# 1P3W_v1p1.net
KiCad netlist of a schematic drawn in EAGLE
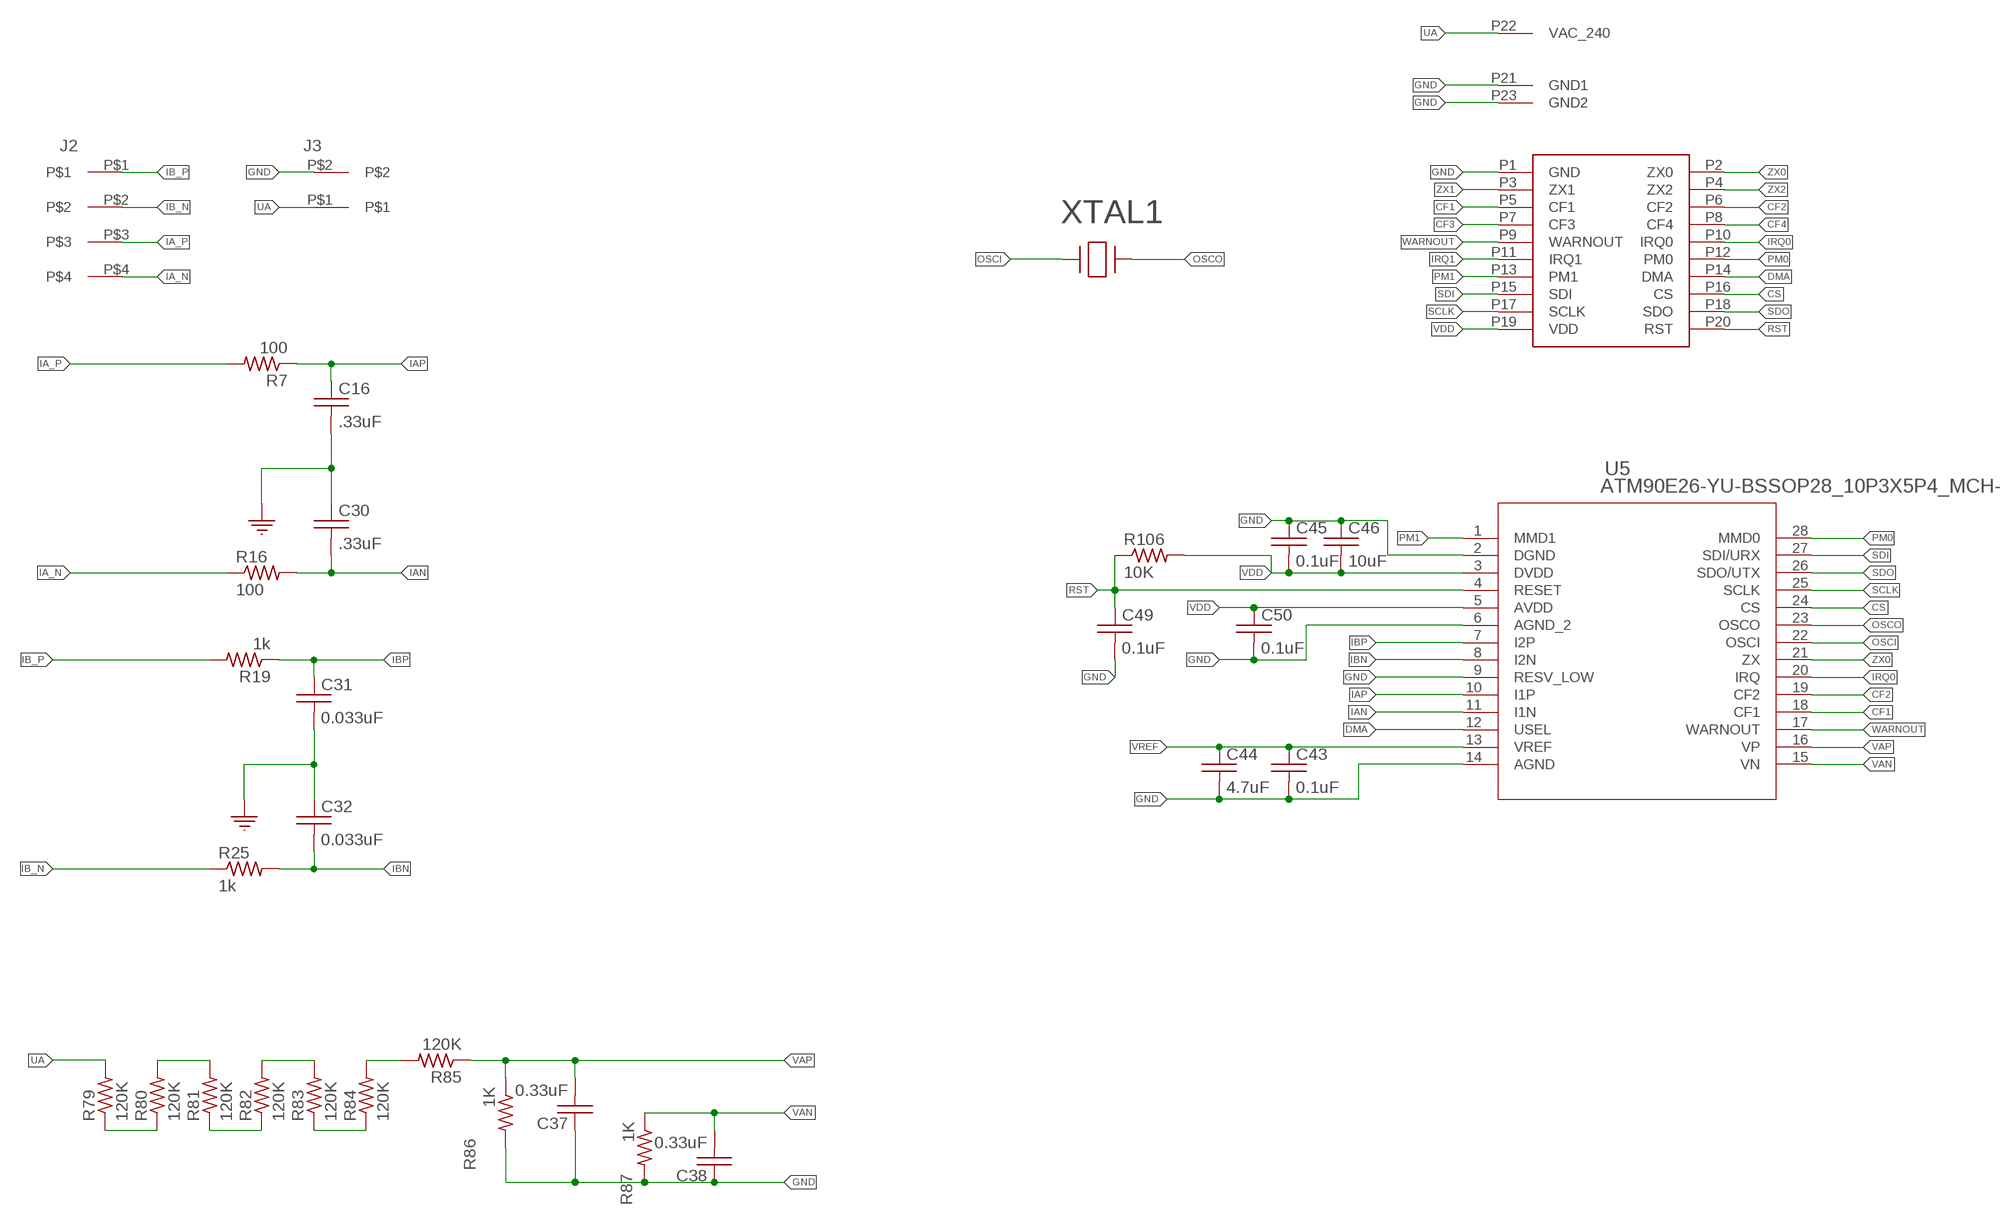
[diagram p0: schematic, sheet 1]

(export (version "E")
  (design (tool "Eeschema 10.0.6"))
  (components
    (comp (ref "C16")
      (value ".33uF")
      (footprint "eagle-import:0402")
      (libsource (lib "eagle-import") (part "C_0402"))
    )
    (comp (ref "C30")
      (value ".33uF")
      (footprint "eagle-import:0402")
      (libsource (lib "eagle-import") (part "C_0402"))
    )
    (comp (ref "C31")
      (value "0.033uF")
      (footprint "eagle-import:0402")
      (libsource (lib "eagle-import") (part "C_0402"))
    )
    (comp (ref "C32")
      (value "0.033uF")
      (footprint "eagle-import:0402")
      (libsource (lib "eagle-import") (part "C_0402"))
    )
    (comp (ref "C37")
      (value "0.33uF")
      (footprint "eagle-import:0402")
      (libsource (lib "eagle-import") (part "C_0402"))
    )
    (comp (ref "C38")
      (value "0.33uF")
      (footprint "eagle-import:0402")
      (libsource (lib "eagle-import") (part "C_0402"))
    )
    (comp (ref "C43")
      (value "0.1uF")
      (footprint "eagle-import:0402")
      (libsource (lib "eagle-import") (part "C_0402"))
    )
    (comp (ref "C44")
      (value "4.7uF")
      (footprint "eagle-import:0402")
      (libsource (lib "eagle-import") (part "C_0402"))
    )
    (comp (ref "C45")
      (value "0.1uF")
      (footprint "eagle-import:0402")
      (libsource (lib "eagle-import") (part "C_0402"))
    )
    (comp (ref "C46")
      (value "10uF")
      (footprint "eagle-import:0402")
      (libsource (lib "eagle-import") (part "C_0402"))
    )
    (comp (ref "C49")
      (value "0.1uF")
      (footprint "eagle-import:0402")
      (libsource (lib "eagle-import") (part "C_0402"))
    )
    (comp (ref "C50")
      (value "0.1uF")
      (footprint "eagle-import:0402")
      (libsource (lib "eagle-import") (part "C_0402"))
    )
    (comp (ref "J2")
      (value "3.81MM_1_X_4_RT_ANGLE_PLUG_HEADER")
      (footprint "eagle-import:1X4_3.81MM_PITCH")
      (libsource (lib "eagle-import") (part "3.81MM_1_X_4_RT_ANGLE_PLUG_HEADER"))
    )
    (comp (ref "J3")
      (value "3.81MM_1_X_2_RT_ANGLE_PLUG_HEADER")
      (footprint "eagle-import:2_3.81MM_PITCH")
      (libsource (lib "eagle-import") (part "3.81MM_1_X_2_RT_ANGLE_PLUG_HEADER"))
    )
    (comp (ref "R7")
      (value "100")
      (footprint "eagle-import:0402")
      (libsource (lib "eagle-import") (part "R_0402"))
    )
    (comp (ref "R16")
      (value "100")
      (footprint "eagle-import:0402")
      (libsource (lib "eagle-import") (part "R_0402"))
    )
    (comp (ref "R19")
      (value "1k")
      (footprint "eagle-import:0402")
      (libsource (lib "eagle-import") (part "R_0402"))
    )
    (comp (ref "R25")
      (value "1k")
      (footprint "eagle-import:0402")
      (libsource (lib "eagle-import") (part "R_0402"))
    )
    (comp (ref "R79")
      (value "120K")
      (footprint "eagle-import:0402")
      (libsource (lib "eagle-import") (part "R_0402"))
    )
    (comp (ref "R80")
      (value "120K")
      (footprint "eagle-import:0402")
      (libsource (lib "eagle-import") (part "R_0402"))
    )
    (comp (ref "R81")
      (value "120K")
      (footprint "eagle-import:0402")
      (libsource (lib "eagle-import") (part "R_0402"))
    )
    (comp (ref "R82")
      (value "120K")
      (footprint "eagle-import:0402")
      (libsource (lib "eagle-import") (part "R_0402"))
    )
    (comp (ref "R83")
      (value "120K")
      (footprint "eagle-import:0402")
      (libsource (lib "eagle-import") (part "R_0402"))
    )
    (comp (ref "R84")
      (value "120K")
      (footprint "eagle-import:0402")
      (libsource (lib "eagle-import") (part "R_0402"))
    )
    (comp (ref "R85")
      (value "120K")
      (footprint "eagle-import:0402")
      (libsource (lib "eagle-import") (part "R_0402"))
    )
    (comp (ref "R86")
      (value "1K")
      (footprint "eagle-import:0402")
      (libsource (lib "eagle-import") (part "R_0402"))
    )
    (comp (ref "R87")
      (value "1K")
      (footprint "eagle-import:0402")
      (libsource (lib "eagle-import") (part "R_0402"))
    )
    (comp (ref "R106")
      (value "10K")
      (footprint "eagle-import:0402")
      (libsource (lib "eagle-import") (part "R_0402"))
    )
    (comp (ref "U$1")
      (value "METER_BASE")
      (footprint "eagle-import:METER_BASE")
      (libsource (lib "eagle-import") (part "METER_BASE"))
    )
    (comp (ref "U5")
      (value "ATM90E26-YU-BSSOP28_10P3X5P4_MCH-M")
      (footprint "eagle-import:SSOP28_10P3X5P4_MCH-M")
      (fields
        (field (name "MANUFACTURER_PART_NUMBER") "ATM90E26-YU-B")
        (field (name "COPYRIGHT") "Copyright (C) 2018 Accelerated Designs. All rights reserved")
      )
      (libsource (lib "eagle-import") (part "ATM90E26-YU-BSSOP28_10P3X5P4_MCH-M"))
    )
    (comp (ref "XTAL1")
      (value "ABLS-8.192MHZ-B2-TXTAL_HC/49US_ABLS_ABR-M")
      (footprint "eagle-import:XTAL_HC_49US_ABLS_ABR-M")
      (fields
        (field (name "MANUFACTURER_PART_NUMBER") "ABLS-8.192MHZ-B2-T")
        (field (name "COPYRIGHT") "Copyright (C) 2018 Accelerated Designs. All rights reserved")
      )
      (libsource (lib "eagle-import") (part "ABLS-8.192MHZ-B2-TXTAL_HC/49US_ABLS_ABR-M"))
    )
  )
  (nets
    (net (code "1") (name "CF1") (class "Default")
      (node (ref "U$1") (pin "P5") (pinfunction "CF1_P5") (pintype "bidirectional"))
      (node (ref "U5") (pin "18") (pinfunction "CF1_18") (pintype "bidirectional"))
    )
    (net (code "2") (name "CF2") (class "Default")
      (node (ref "U$1") (pin "P6") (pinfunction "CF2_P6") (pintype "bidirectional"))
      (node (ref "U5") (pin "19") (pinfunction "CF2_19") (pintype "bidirectional"))
    )
    (net (code "3") (name "CF3") (class "Default")
      (node (ref "U$1") (pin "P7") (pinfunction "CF3_P7") (pintype "bidirectional"))
    )
    (net (code "4") (name "CF4") (class "Default")
      (node (ref "U$1") (pin "P8") (pinfunction "CF4_P8") (pintype "bidirectional"))
    )
    (net (code "5") (name "CS") (class "Default")
      (node (ref "U$1") (pin "P16") (pinfunction "CS_P16") (pintype "bidirectional"))
      (node (ref "U5") (pin "24") (pinfunction "CS_24") (pintype "passive"))
    )
    (net (code "6") (name "DMA") (class "Default")
      (node (ref "U$1") (pin "P14") (pinfunction "DMA_P14") (pintype "bidirectional"))
      (node (ref "U5") (pin "12") (pinfunction "USEL_12") (pintype "passive"))
    )
    (net (code "7") (name "GND") (class "Default")
      (node (ref "C16") (pin "P$2") (pinfunction "2_P$2") (pintype "passive"))
      (node (ref "C30") (pin "P$1") (pinfunction "1_P$1") (pintype "passive"))
      (node (ref "C31") (pin "P$2") (pinfunction "2_P$2") (pintype "passive"))
      (node (ref "C32") (pin "P$1") (pinfunction "1_P$1") (pintype "passive"))
      (node (ref "C37") (pin "P$1") (pinfunction "1_P$1") (pintype "passive"))
      (node (ref "C38") (pin "P$1") (pinfunction "1_P$1") (pintype "passive"))
      (node (ref "C43") (pin "P$2") (pinfunction "2_P$2") (pintype "passive"))
      (node (ref "C44") (pin "P$2") (pinfunction "2_P$2") (pintype "passive"))
      (node (ref "C45") (pin "P$1") (pinfunction "1_P$1") (pintype "passive"))
      (node (ref "C46") (pin "P$1") (pinfunction "1_P$1") (pintype "passive"))
      (node (ref "C49") (pin "P$2") (pinfunction "2_P$2") (pintype "passive"))
      (node (ref "C50") (pin "P$2") (pinfunction "2_P$2") (pintype "passive"))
      (node (ref "J3") (pin "P$2") (pinfunction "P$2_P$2") (pintype "bidirectional"))
      (node (ref "R86") (pin "P$2") (pinfunction "2_P$2") (pintype "passive"))
      (node (ref "R87") (pin "P$2") (pinfunction "2_P$2") (pintype "passive"))
      (node (ref "U$1") (pin "P1") (pinfunction "GND_P1") (pintype "bidirectional"))
      (node (ref "U$1") (pin "P21") (pinfunction "GND1_P21") (pintype "bidirectional"))
      (node (ref "U$1") (pin "P23") (pinfunction "GND2_P23") (pintype "bidirectional"))
      (node (ref "U5") (pin "14") (pinfunction "AGND_14") (pintype "passive"))
      (node (ref "U5") (pin "2") (pinfunction "DGND_2") (pintype "passive"))
      (node (ref "U5") (pin "6") (pinfunction "AGND_2_6") (pintype "passive"))
      (node (ref "U5") (pin "9") (pinfunction "RESV_LOW_9") (pintype "passive"))
    )
    (net (code "8") (name "IAN") (class "Default")
      (node (ref "C30") (pin "P$2") (pinfunction "2_P$2") (pintype "passive"))
      (node (ref "R16") (pin "P$2") (pinfunction "2_P$2") (pintype "passive"))
      (node (ref "U5") (pin "11") (pinfunction "I1N_11") (pintype "bidirectional"))
    )
    (net (code "9") (name "IAP") (class "Default")
      (node (ref "C16") (pin "P$1") (pinfunction "1_P$1") (pintype "passive"))
      (node (ref "R7") (pin "P$1") (pinfunction "1_P$1") (pintype "passive"))
      (node (ref "U5") (pin "10") (pinfunction "I1P_10") (pintype "bidirectional"))
    )
    (net (code "10") (name "IA_N") (class "Default")
      (node (ref "J2") (pin "P$4") (pinfunction "P$4_P$4") (pintype "bidirectional"))
      (node (ref "R16") (pin "P$1") (pinfunction "1_P$1") (pintype "passive"))
    )
    (net (code "11") (name "IA_P") (class "Default")
      (node (ref "J2") (pin "P$3") (pinfunction "P$3_P$3") (pintype "bidirectional"))
      (node (ref "R7") (pin "P$2") (pinfunction "2_P$2") (pintype "passive"))
    )
    (net (code "12") (name "IBN") (class "Default")
      (node (ref "C32") (pin "P$2") (pinfunction "2_P$2") (pintype "passive"))
      (node (ref "R25") (pin "P$2") (pinfunction "2_P$2") (pintype "passive"))
      (node (ref "U5") (pin "8") (pinfunction "I2N_8") (pintype "bidirectional"))
    )
    (net (code "13") (name "IBP") (class "Default")
      (node (ref "C31") (pin "P$1") (pinfunction "1_P$1") (pintype "passive"))
      (node (ref "R19") (pin "P$1") (pinfunction "1_P$1") (pintype "passive"))
      (node (ref "U5") (pin "7") (pinfunction "I2P_7") (pintype "bidirectional"))
    )
    (net (code "14") (name "IB_N") (class "Default")
      (node (ref "J2") (pin "P$2") (pinfunction "P$2_P$2") (pintype "bidirectional"))
      (node (ref "R25") (pin "P$1") (pinfunction "1_P$1") (pintype "passive"))
    )
    (net (code "15") (name "IB_P") (class "Default")
      (node (ref "J2") (pin "P$1") (pinfunction "P$1_P$1") (pintype "bidirectional"))
      (node (ref "R19") (pin "P$2") (pinfunction "2_P$2") (pintype "passive"))
    )
    (net (code "16") (name "IRQ0") (class "Default")
      (node (ref "U$1") (pin "P10") (pinfunction "IRQ0_P10") (pintype "bidirectional"))
      (node (ref "U5") (pin "20") (pinfunction "IRQ_20") (pintype "passive"))
    )
    (net (code "17") (name "IRQ1") (class "Default")
      (node (ref "U$1") (pin "P11") (pinfunction "IRQ1_P11") (pintype "bidirectional"))
    )
    (net (code "18") (name "Net-(R79-1)") (class "Default")
      (node (ref "R79") (pin "P$1") (pinfunction "1_P$1") (pintype "passive"))
      (node (ref "R80") (pin "P$1") (pinfunction "1_P$1") (pintype "passive"))
    )
    (net (code "19") (name "Net-(R80-2)") (class "Default")
      (node (ref "R80") (pin "P$2") (pinfunction "2_P$2") (pintype "passive"))
      (node (ref "R81") (pin "P$2") (pinfunction "2_P$2") (pintype "passive"))
    )
    (net (code "20") (name "Net-(R81-1)") (class "Default")
      (node (ref "R81") (pin "P$1") (pinfunction "1_P$1") (pintype "passive"))
      (node (ref "R82") (pin "P$1") (pinfunction "1_P$1") (pintype "passive"))
    )
    (net (code "21") (name "Net-(R82-2)") (class "Default")
      (node (ref "R82") (pin "P$2") (pinfunction "2_P$2") (pintype "passive"))
      (node (ref "R83") (pin "P$2") (pinfunction "2_P$2") (pintype "passive"))
    )
    (net (code "22") (name "Net-(R83-1)") (class "Default")
      (node (ref "R83") (pin "P$1") (pinfunction "1_P$1") (pintype "passive"))
      (node (ref "R84") (pin "P$1") (pinfunction "1_P$1") (pintype "passive"))
    )
    (net (code "23") (name "Net-(R84-2)") (class "Default")
      (node (ref "R84") (pin "P$2") (pinfunction "2_P$2") (pintype "passive"))
      (node (ref "R85") (pin "P$2") (pinfunction "2_P$2") (pintype "passive"))
    )
    (net (code "24") (name "OSCI") (class "Default")
      (node (ref "U5") (pin "22") (pinfunction "OSCI_22") (pintype "passive"))
      (node (ref "XTAL1") (pin "1") (pinfunction "1_1") (pintype "passive"))
    )
    (net (code "25") (name "OSCO") (class "Default")
      (node (ref "U5") (pin "23") (pinfunction "OSCO_23") (pintype "passive"))
      (node (ref "XTAL1") (pin "2") (pinfunction "2_2") (pintype "passive"))
    )
    (net (code "26") (name "PM0") (class "Default")
      (node (ref "U$1") (pin "P12") (pinfunction "PM0_P12") (pintype "bidirectional"))
      (node (ref "U5") (pin "28") (pinfunction "MMD0_28") (pintype "bidirectional"))
    )
    (net (code "27") (name "PM1") (class "Default")
      (node (ref "U$1") (pin "P13") (pinfunction "PM1_P13") (pintype "bidirectional"))
      (node (ref "U5") (pin "1") (pinfunction "MMD1_1") (pintype "bidirectional"))
    )
    (net (code "28") (name "RST") (class "Default")
      (node (ref "C49") (pin "P$1") (pinfunction "1_P$1") (pintype "passive"))
      (node (ref "R106") (pin "P$1") (pinfunction "1_P$1") (pintype "passive"))
      (node (ref "U$1") (pin "P20") (pinfunction "RST_P20") (pintype "bidirectional"))
      (node (ref "U5") (pin "4") (pinfunction "RESET_4") (pintype "passive"))
    )
    (net (code "29") (name "SCLK") (class "Default")
      (node (ref "U$1") (pin "P17") (pinfunction "SCLK_P17") (pintype "bidirectional"))
      (node (ref "U5") (pin "25") (pinfunction "SCLK_25") (pintype "passive"))
    )
    (net (code "30") (name "SDI") (class "Default")
      (node (ref "U$1") (pin "P15") (pinfunction "SDI_P15") (pintype "bidirectional"))
      (node (ref "U5") (pin "27") (pinfunction "SDI/URX_27") (pintype "passive"))
    )
    (net (code "31") (name "SDO") (class "Default")
      (node (ref "U$1") (pin "P18") (pinfunction "SDO_P18") (pintype "bidirectional"))
      (node (ref "U5") (pin "26") (pinfunction "SDO/UTX_26") (pintype "passive"))
    )
    (net (code "32") (name "UA") (class "Default")
      (node (ref "J3") (pin "P$1") (pinfunction "P$1_P$1") (pintype "bidirectional"))
      (node (ref "R79") (pin "P$2") (pinfunction "2_P$2") (pintype "passive"))
      (node (ref "U$1") (pin "P22") (pinfunction "VAC_240_P22") (pintype "bidirectional"))
    )
    (net (code "33") (name "VAN") (class "Default")
      (node (ref "C38") (pin "P$2") (pinfunction "2_P$2") (pintype "passive"))
      (node (ref "R87") (pin "P$1") (pinfunction "1_P$1") (pintype "passive"))
      (node (ref "U5") (pin "15") (pinfunction "VN_15") (pintype "passive"))
    )
    (net (code "34") (name "VAP") (class "Default")
      (node (ref "C37") (pin "P$2") (pinfunction "2_P$2") (pintype "passive"))
      (node (ref "R85") (pin "P$1") (pinfunction "1_P$1") (pintype "passive"))
      (node (ref "R86") (pin "P$1") (pinfunction "1_P$1") (pintype "passive"))
      (node (ref "U5") (pin "16") (pinfunction "VP_16") (pintype "passive"))
    )
    (net (code "35") (name "VDD") (class "Default")
      (node (ref "C45") (pin "P$2") (pinfunction "2_P$2") (pintype "passive"))
      (node (ref "C46") (pin "P$2") (pinfunction "2_P$2") (pintype "passive"))
      (node (ref "C50") (pin "P$1") (pinfunction "1_P$1") (pintype "passive"))
      (node (ref "R106") (pin "P$2") (pinfunction "2_P$2") (pintype "passive"))
      (node (ref "U$1") (pin "P19") (pinfunction "VDD_P19") (pintype "bidirectional"))
      (node (ref "U5") (pin "3") (pinfunction "DVDD_3") (pintype "power_in"))
      (node (ref "U5") (pin "5") (pinfunction "AVDD_5") (pintype "power_in"))
    )
    (net (code "36") (name "VREF") (class "Default")
      (node (ref "C43") (pin "P$1") (pinfunction "1_P$1") (pintype "passive"))
      (node (ref "C44") (pin "P$1") (pinfunction "1_P$1") (pintype "passive"))
      (node (ref "U5") (pin "13") (pinfunction "VREF_13") (pintype "power_in"))
    )
    (net (code "37") (name "WARNOUT") (class "Default")
      (node (ref "U$1") (pin "P9") (pinfunction "WARNOUT_P9") (pintype "bidirectional"))
      (node (ref "U5") (pin "17") (pinfunction "WARNOUT_17") (pintype "output"))
    )
    (net (code "38") (name "ZX0") (class "Default")
      (node (ref "U$1") (pin "P2") (pinfunction "ZX0_P2") (pintype "bidirectional"))
      (node (ref "U5") (pin "21") (pinfunction "ZX_21") (pintype "passive"))
    )
    (net (code "39") (name "ZX1") (class "Default")
      (node (ref "U$1") (pin "P3") (pinfunction "ZX1_P3") (pintype "bidirectional"))
    )
    (net (code "40") (name "ZX2") (class "Default")
      (node (ref "U$1") (pin "P4") (pinfunction "ZX2_P4") (pintype "bidirectional"))
    )
  )
)
